# MBO.net
KiCad netlist of a schematic drawn in EAGLE
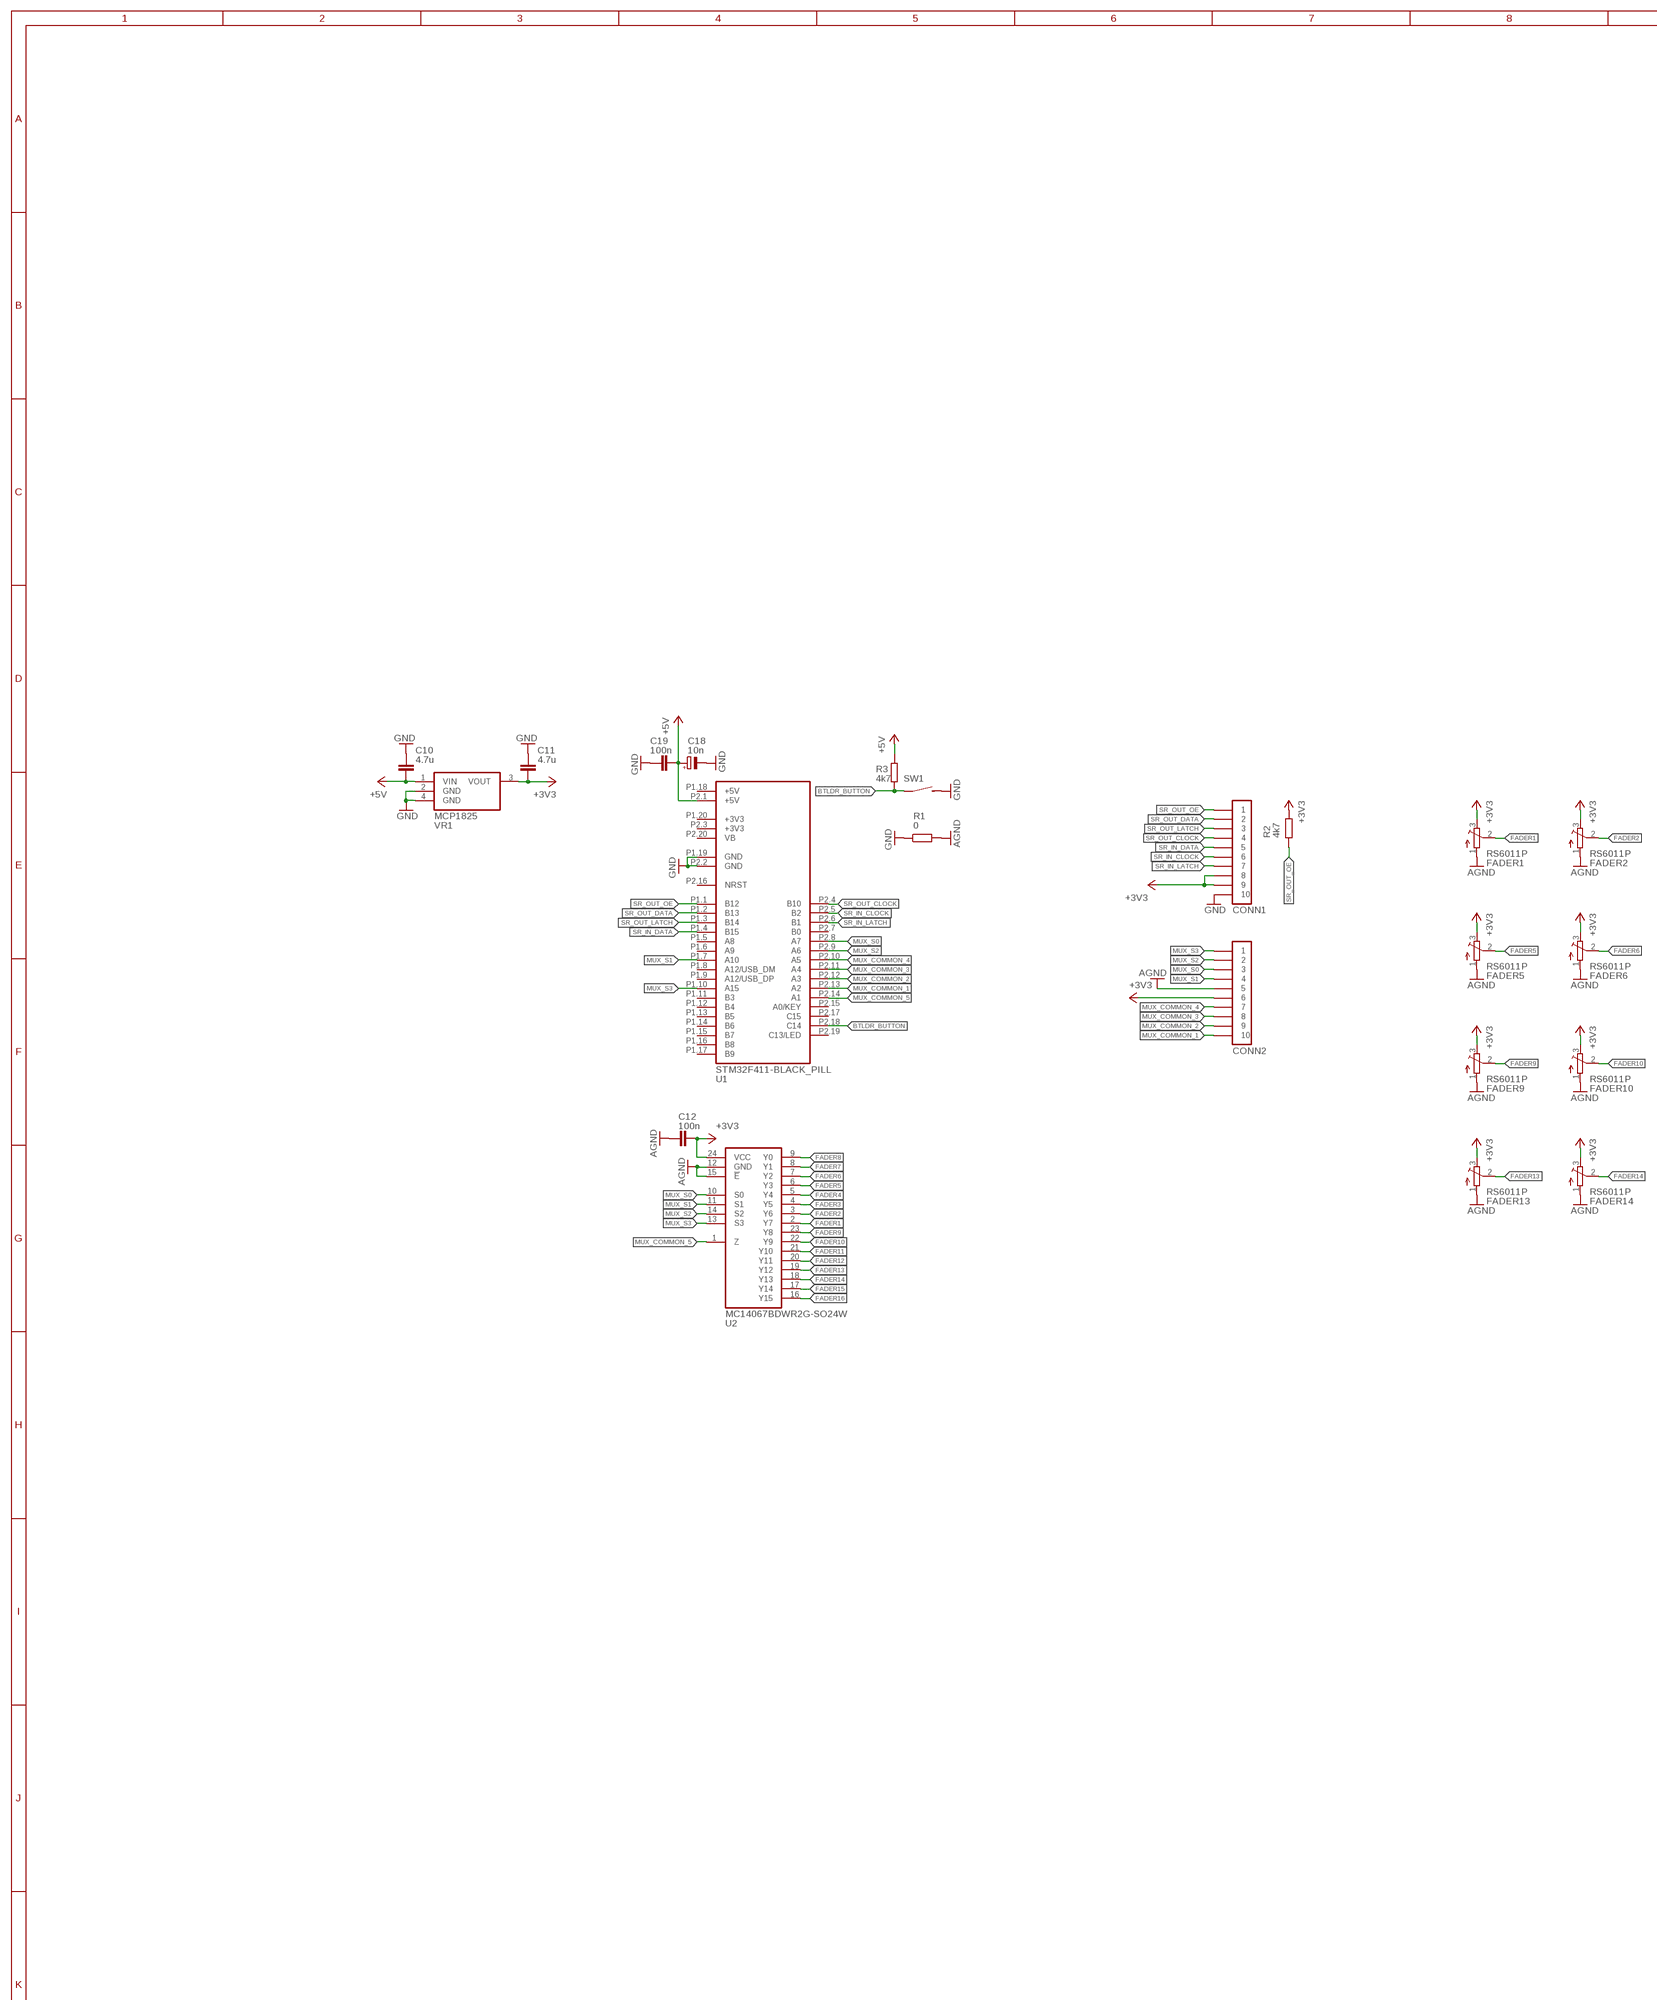
[diagram p0: schematic, sheet 1, part 1 of 3]
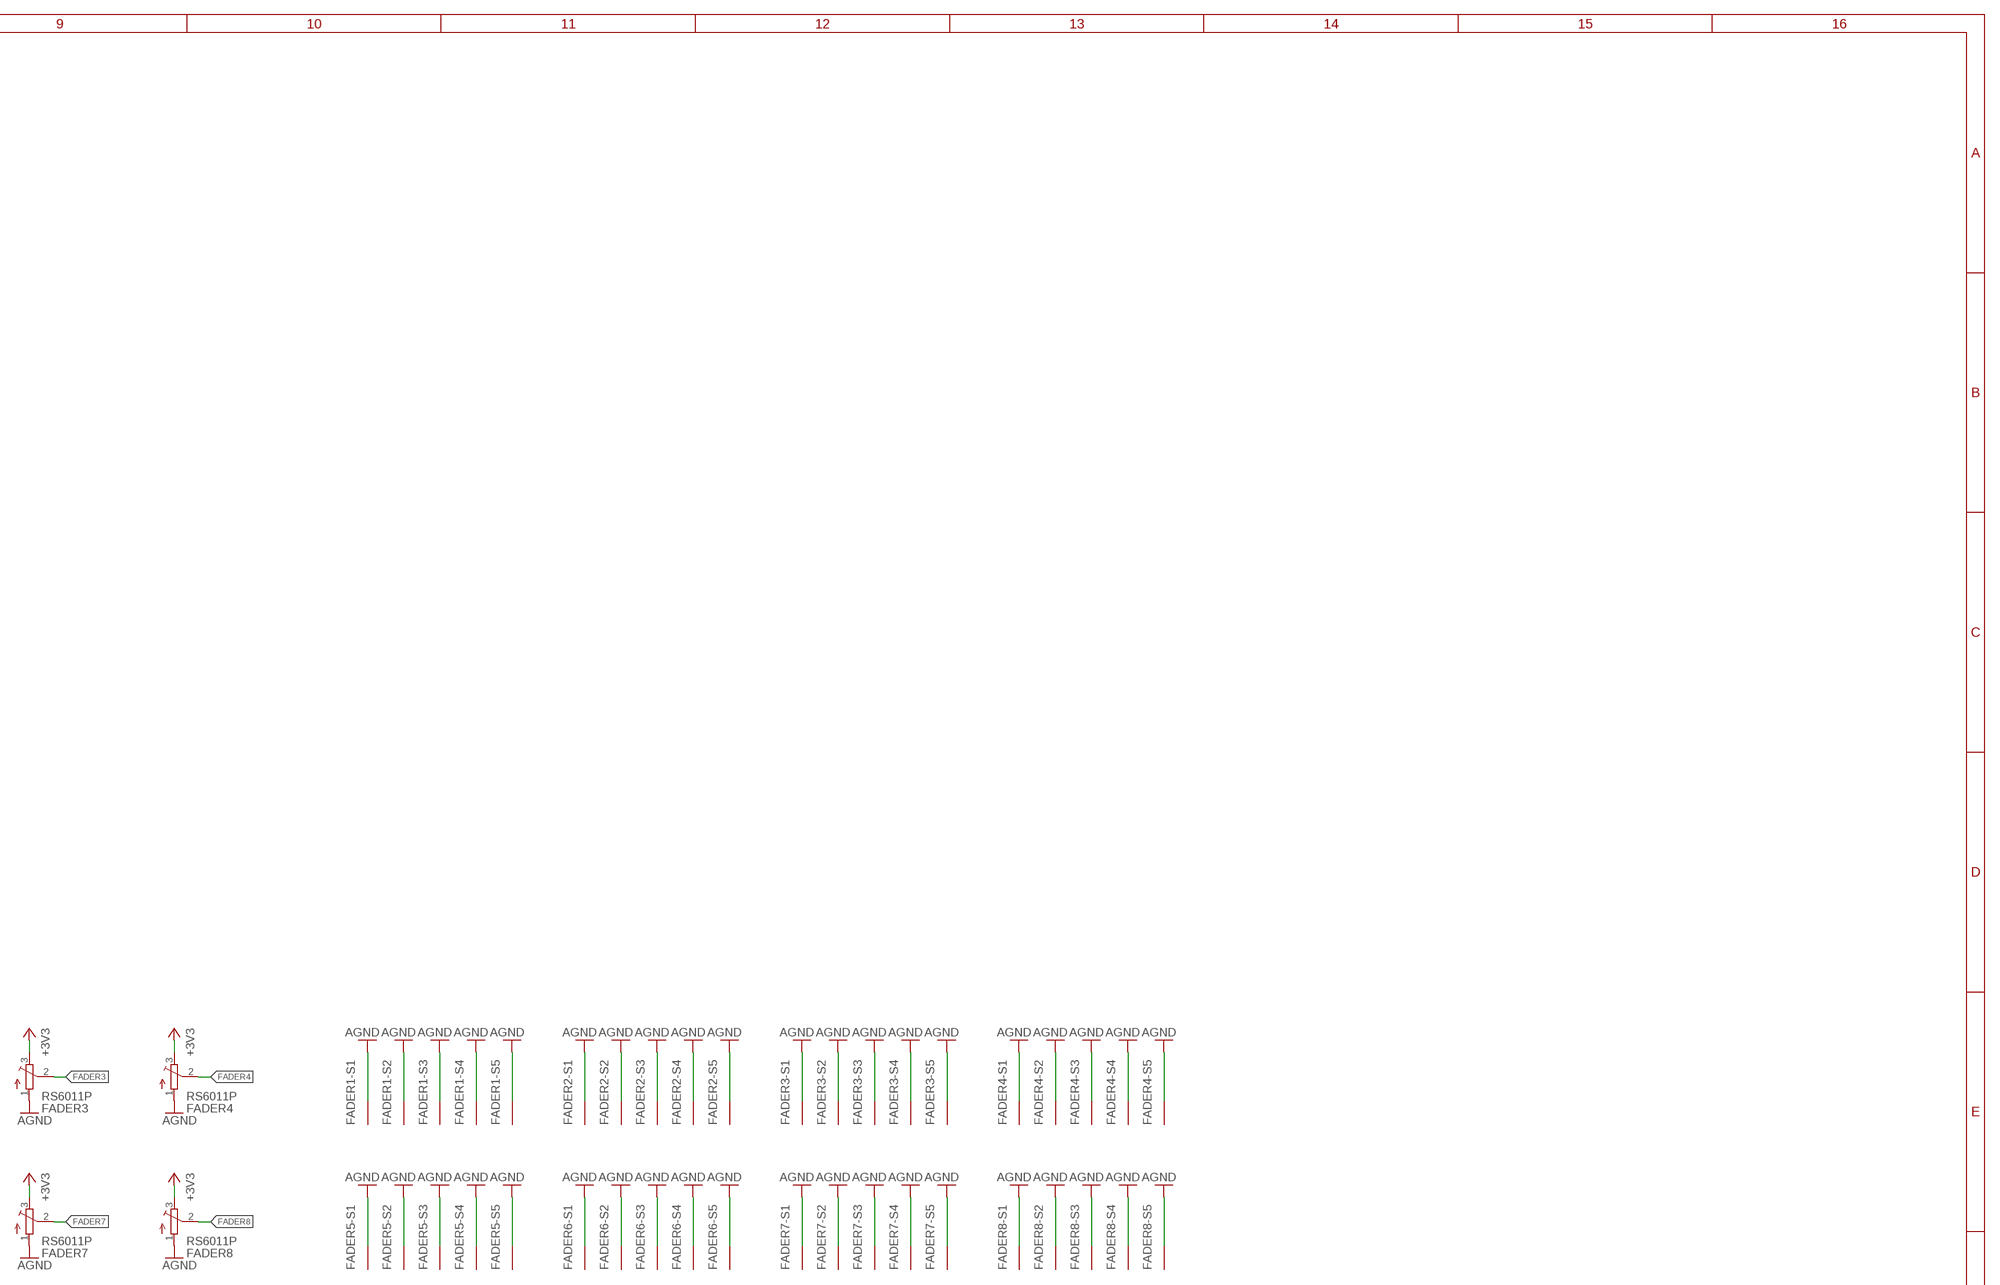
[diagram p1: schematic, sheet 1, part 2 of 3]
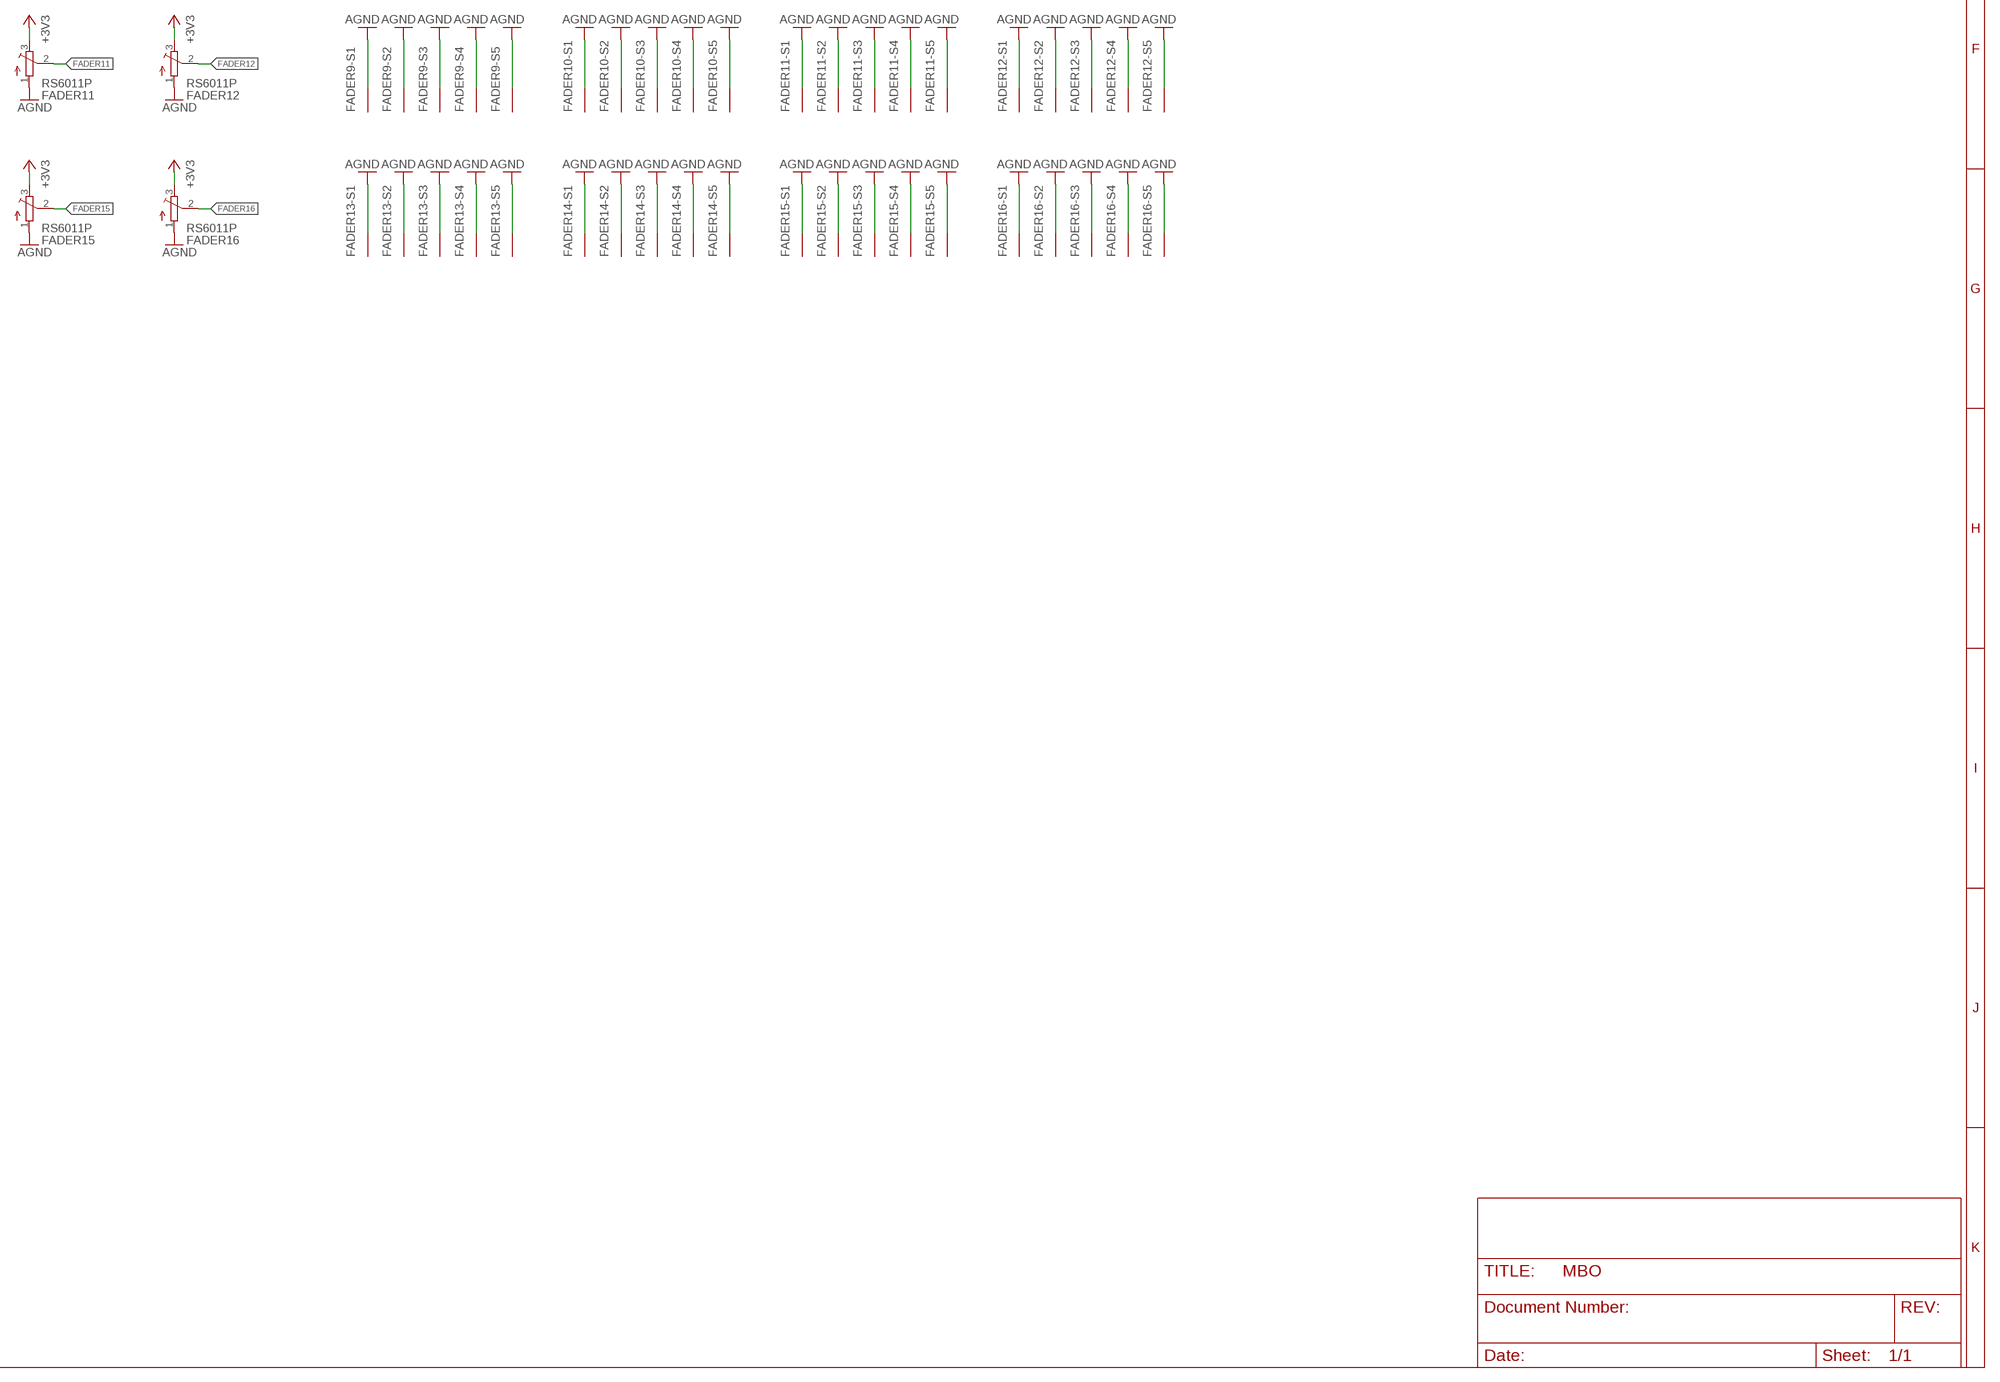
[diagram p2: schematic, sheet 1, part 3 of 3]

(export (version "E")
  (design (tool "Eeschema 10.0.6"))
  (components
    (comp (ref "C10")
      (value "4.7u")
      (footprint "eagle-import:C0805")
      (libsource (lib "eagle-import") (part "CAPACITOR-0805"))
    )
    (comp (ref "C11")
      (value "4.7u")
      (footprint "eagle-import:C0805")
      (libsource (lib "eagle-import") (part "CAPACITOR-0805"))
    )
    (comp (ref "C12")
      (value "100n")
      (footprint "eagle-import:C0805")
      (libsource (lib "eagle-import") (part "CAPACITOR-0805"))
    )
    (comp (ref "C18")
      (value "10n")
      (footprint "eagle-import:C-TH-E-0401")
      (libsource (lib "eagle-import") (part "ELECTROLYTIC_CAPACITOR-C-TH-E-0401"))
    )
    (comp (ref "C19")
      (value "100n")
      (footprint "eagle-import:C0805")
      (libsource (lib "eagle-import") (part "CAPACITOR-0805"))
    )
    (comp (ref "CONN1")
      (value "PINHD-1X10-FFC-1MM-Z")
      (footprint "eagle-import:MOLEX-52271-1079")
      (fields (field (name "MANUFACTURER") "Molex") (field (name "MPN") "52271-1079"))
      (libsource (lib "eagle-import") (part "PINHD-1X10-FFC-1MM-Z"))
    )
    (comp (ref "CONN2")
      (value "PINHD-1X10-FFC-1MM-Z")
      (footprint "eagle-import:MOLEX-52271-1079")
      (fields (field (name "MANUFACTURER") "Molex") (field (name "MPN") "52271-1079"))
      (libsource (lib "eagle-import") (part "PINHD-1X10-FFC-1MM-Z"))
    )
    (comp (ref "FADER1")
      (value "RS6011P")
      (footprint "eagle-import:RS6011_P")
      (libsource (lib "eagle-import") (part "RS6011P"))
    )
    (comp (ref "FADER2")
      (value "RS6011P")
      (footprint "eagle-import:RS6011_P")
      (libsource (lib "eagle-import") (part "RS6011P"))
    )
    (comp (ref "FADER3")
      (value "RS6011P")
      (footprint "eagle-import:RS6011_P")
      (libsource (lib "eagle-import") (part "RS6011P"))
    )
    (comp (ref "FADER4")
      (value "RS6011P")
      (footprint "eagle-import:RS6011_P")
      (libsource (lib "eagle-import") (part "RS6011P"))
    )
    (comp (ref "FADER5")
      (value "RS6011P")
      (footprint "eagle-import:RS6011_P")
      (libsource (lib "eagle-import") (part "RS6011P"))
    )
    (comp (ref "FADER6")
      (value "RS6011P")
      (footprint "eagle-import:RS6011_P")
      (libsource (lib "eagle-import") (part "RS6011P"))
    )
    (comp (ref "FADER7")
      (value "RS6011P")
      (footprint "eagle-import:RS6011_P")
      (libsource (lib "eagle-import") (part "RS6011P"))
    )
    (comp (ref "FADER8")
      (value "RS6011P")
      (footprint "eagle-import:RS6011_P")
      (libsource (lib "eagle-import") (part "RS6011P"))
    )
    (comp (ref "FADER9")
      (value "RS6011P")
      (footprint "eagle-import:RS6011_P")
      (libsource (lib "eagle-import") (part "RS6011P"))
    )
    (comp (ref "FADER10")
      (value "RS6011P")
      (footprint "eagle-import:RS6011_P")
      (libsource (lib "eagle-import") (part "RS6011P"))
    )
    (comp (ref "FADER11")
      (value "RS6011P")
      (footprint "eagle-import:RS6011_P")
      (libsource (lib "eagle-import") (part "RS6011P"))
    )
    (comp (ref "FADER12")
      (value "RS6011P")
      (footprint "eagle-import:RS6011_P")
      (libsource (lib "eagle-import") (part "RS6011P"))
    )
    (comp (ref "FADER13")
      (value "RS6011P")
      (footprint "eagle-import:RS6011_P")
      (libsource (lib "eagle-import") (part "RS6011P"))
    )
    (comp (ref "FADER14")
      (value "RS6011P")
      (footprint "eagle-import:RS6011_P")
      (libsource (lib "eagle-import") (part "RS6011P"))
    )
    (comp (ref "FADER15")
      (value "RS6011P")
      (footprint "eagle-import:RS6011_P")
      (libsource (lib "eagle-import") (part "RS6011P"))
    )
    (comp (ref "FADER16")
      (value "RS6011P")
      (footprint "eagle-import:RS6011_P")
      (libsource (lib "eagle-import") (part "RS6011P"))
    )
    (comp (ref "R1")
      (value "0")
      (footprint "eagle-import:R0805")
      (libsource (lib "eagle-import") (part "RESISTOR-0805"))
    )
    (comp (ref "R2")
      (value "4k7")
      (footprint "eagle-import:R0805")
      (libsource (lib "eagle-import") (part "RESISTOR-0805"))
    )
    (comp (ref "R3")
      (value "4k7")
      (footprint "eagle-import:R0805")
      (libsource (lib "eagle-import") (part "RESISTOR-0805"))
    )
    (comp (ref "SW1")
      (value "SWITCH-TACT-TH-6X6MM")
      (footprint "eagle-import:TACT_SW_6X6MM")
      (libsource (lib "eagle-import") (part "SWITCH-TACT-TH-6X6MM"))
    )
    (comp (ref "U1")
      (value "STM32F411-BLACK_PILL")
      (footprint "eagle-import:STM32F411-BLACK_PILL")
      (libsource (lib "eagle-import") (part "STM32F411-BLACK_PILL"))
    )
    (comp (ref "U2")
      (value "MC14067BDWR2G-SO24W")
      (footprint "eagle-import:SO24-W")
      (fields (field (name "MANUFACTURER") "ON Semiconductor") (field (name "MPN") "MC14067BDWR2G"))
      (libsource (lib "eagle-import") (part "MC14067BDWR2G-SO24W"))
    )
    (comp (ref "VR1")
      (value "MCP1825")
      (footprint "eagle-import:SOT223")
      (fields (field (name "MANUFACTURER") "Microchip") (field (name "MPN") "MCP1825S-3302E/DB"))
      (libsource (lib "eagle-import") (part "MCP1825"))
    )
  )
  (nets
    (net (code "1") (name "+3V3") (class "Default")
      (node (ref "C11") (pin "1") (pinfunction "1_1") (pintype "passive"))
      (node (ref "C12") (pin "1") (pinfunction "1_1") (pintype "passive"))
      (node (ref "CONN1") (pin "8") (pinfunction "8_8") (pintype "passive"))
      (node (ref "CONN1") (pin "9") (pinfunction "9_9") (pintype "passive"))
      (node (ref "CONN2") (pin "6") (pinfunction "6_6") (pintype "passive"))
      (node (ref "FADER1") (pin "3") (pinfunction "3_3") (pintype "passive"))
      (node (ref "FADER10") (pin "3") (pinfunction "3_3") (pintype "passive"))
      (node (ref "FADER11") (pin "3") (pinfunction "3_3") (pintype "passive"))
      (node (ref "FADER12") (pin "3") (pinfunction "3_3") (pintype "passive"))
      (node (ref "FADER13") (pin "3") (pinfunction "3_3") (pintype "passive"))
      (node (ref "FADER14") (pin "3") (pinfunction "3_3") (pintype "passive"))
      (node (ref "FADER15") (pin "3") (pinfunction "3_3") (pintype "passive"))
      (node (ref "FADER16") (pin "3") (pinfunction "3_3") (pintype "passive"))
      (node (ref "FADER2") (pin "3") (pinfunction "3_3") (pintype "passive"))
      (node (ref "FADER3") (pin "3") (pinfunction "3_3") (pintype "passive"))
      (node (ref "FADER4") (pin "3") (pinfunction "3_3") (pintype "passive"))
      (node (ref "FADER5") (pin "3") (pinfunction "3_3") (pintype "passive"))
      (node (ref "FADER6") (pin "3") (pinfunction "3_3") (pintype "passive"))
      (node (ref "FADER7") (pin "3") (pinfunction "3_3") (pintype "passive"))
      (node (ref "FADER8") (pin "3") (pinfunction "3_3") (pintype "passive"))
      (node (ref "FADER9") (pin "3") (pinfunction "3_3") (pintype "passive"))
      (node (ref "R2") (pin "2") (pinfunction "2_2") (pintype "passive"))
      (node (ref "U2") (pin "24") (pinfunction "VCC_24") (pintype "passive"))
      (node (ref "VR1") (pin "3") (pinfunction "VOUT_3") (pintype "passive"))
    )
    (net (code "2") (name "+5V") (class "Default")
      (node (ref "C10") (pin "1") (pinfunction "1_1") (pintype "passive"))
      (node (ref "C18") (pin "+") (pinfunction "+_+") (pintype "passive"))
      (node (ref "C19") (pin "1") (pinfunction "1_1") (pintype "passive"))
      (node (ref "R3") (pin "1") (pinfunction "1_1") (pintype "passive"))
      (node (ref "U1") (pin "P2.1") (pinfunction "+5V_P2.1") (pintype "bidirectional"))
      (node (ref "VR1") (pin "1") (pinfunction "VIN_1") (pintype "passive"))
    )
    (net (code "3") (name "AGND") (class "Default")
      (node (ref "C12") (pin "2") (pinfunction "2_2") (pintype "passive"))
      (node (ref "CONN2") (pin "5") (pinfunction "5_5") (pintype "passive"))
      (node (ref "FADER1") (pin "1") (pinfunction "1_1") (pintype "passive"))
      (node (ref "FADER1") (pin "S1") (pinfunction "S_S1") (pintype "passive"))
      (node (ref "FADER1") (pin "S2") (pinfunction "S_S2") (pintype "passive"))
      (node (ref "FADER1") (pin "S3") (pinfunction "S_S3") (pintype "passive"))
      (node (ref "FADER1") (pin "S4") (pinfunction "S_S4") (pintype "passive"))
      (node (ref "FADER1") (pin "S5") (pinfunction "S_S5") (pintype "passive"))
      (node (ref "FADER10") (pin "1") (pinfunction "1_1") (pintype "passive"))
      (node (ref "FADER10") (pin "S1") (pinfunction "S_S1") (pintype "passive"))
      (node (ref "FADER10") (pin "S2") (pinfunction "S_S2") (pintype "passive"))
      (node (ref "FADER10") (pin "S3") (pinfunction "S_S3") (pintype "passive"))
      (node (ref "FADER10") (pin "S4") (pinfunction "S_S4") (pintype "passive"))
      (node (ref "FADER10") (pin "S5") (pinfunction "S_S5") (pintype "passive"))
      (node (ref "FADER11") (pin "1") (pinfunction "1_1") (pintype "passive"))
      (node (ref "FADER11") (pin "S1") (pinfunction "S_S1") (pintype "passive"))
      (node (ref "FADER11") (pin "S2") (pinfunction "S_S2") (pintype "passive"))
      (node (ref "FADER11") (pin "S3") (pinfunction "S_S3") (pintype "passive"))
      (node (ref "FADER11") (pin "S4") (pinfunction "S_S4") (pintype "passive"))
      (node (ref "FADER11") (pin "S5") (pinfunction "S_S5") (pintype "passive"))
      (node (ref "FADER12") (pin "1") (pinfunction "1_1") (pintype "passive"))
      (node (ref "FADER12") (pin "S1") (pinfunction "S_S1") (pintype "passive"))
      (node (ref "FADER12") (pin "S2") (pinfunction "S_S2") (pintype "passive"))
      (node (ref "FADER12") (pin "S3") (pinfunction "S_S3") (pintype "passive"))
      (node (ref "FADER12") (pin "S4") (pinfunction "S_S4") (pintype "passive"))
      (node (ref "FADER12") (pin "S5") (pinfunction "S_S5") (pintype "passive"))
      (node (ref "FADER13") (pin "1") (pinfunction "1_1") (pintype "passive"))
      (node (ref "FADER13") (pin "S1") (pinfunction "S_S1") (pintype "passive"))
      (node (ref "FADER13") (pin "S2") (pinfunction "S_S2") (pintype "passive"))
      (node (ref "FADER13") (pin "S3") (pinfunction "S_S3") (pintype "passive"))
      (node (ref "FADER13") (pin "S4") (pinfunction "S_S4") (pintype "passive"))
      (node (ref "FADER13") (pin "S5") (pinfunction "S_S5") (pintype "passive"))
      (node (ref "FADER14") (pin "1") (pinfunction "1_1") (pintype "passive"))
      (node (ref "FADER14") (pin "S1") (pinfunction "S_S1") (pintype "passive"))
      (node (ref "FADER14") (pin "S2") (pinfunction "S_S2") (pintype "passive"))
      (node (ref "FADER14") (pin "S3") (pinfunction "S_S3") (pintype "passive"))
      (node (ref "FADER14") (pin "S4") (pinfunction "S_S4") (pintype "passive"))
      (node (ref "FADER14") (pin "S5") (pinfunction "S_S5") (pintype "passive"))
      (node (ref "FADER15") (pin "1") (pinfunction "1_1") (pintype "passive"))
      (node (ref "FADER15") (pin "S1") (pinfunction "S_S1") (pintype "passive"))
      (node (ref "FADER15") (pin "S2") (pinfunction "S_S2") (pintype "passive"))
      (node (ref "FADER15") (pin "S3") (pinfunction "S_S3") (pintype "passive"))
      (node (ref "FADER15") (pin "S4") (pinfunction "S_S4") (pintype "passive"))
      (node (ref "FADER15") (pin "S5") (pinfunction "S_S5") (pintype "passive"))
      (node (ref "FADER16") (pin "1") (pinfunction "1_1") (pintype "passive"))
      (node (ref "FADER16") (pin "S1") (pinfunction "S_S1") (pintype "passive"))
      (node (ref "FADER16") (pin "S2") (pinfunction "S_S2") (pintype "passive"))
      (node (ref "FADER16") (pin "S3") (pinfunction "S_S3") (pintype "passive"))
      (node (ref "FADER16") (pin "S4") (pinfunction "S_S4") (pintype "passive"))
      (node (ref "FADER16") (pin "S5") (pinfunction "S_S5") (pintype "passive"))
      (node (ref "FADER2") (pin "1") (pinfunction "1_1") (pintype "passive"))
      (node (ref "FADER2") (pin "S1") (pinfunction "S_S1") (pintype "passive"))
      (node (ref "FADER2") (pin "S2") (pinfunction "S_S2") (pintype "passive"))
      (node (ref "FADER2") (pin "S3") (pinfunction "S_S3") (pintype "passive"))
      (node (ref "FADER2") (pin "S4") (pinfunction "S_S4") (pintype "passive"))
      (node (ref "FADER2") (pin "S5") (pinfunction "S_S5") (pintype "passive"))
      (node (ref "FADER3") (pin "1") (pinfunction "1_1") (pintype "passive"))
      (node (ref "FADER3") (pin "S1") (pinfunction "S_S1") (pintype "passive"))
      (node (ref "FADER3") (pin "S2") (pinfunction "S_S2") (pintype "passive"))
      (node (ref "FADER3") (pin "S3") (pinfunction "S_S3") (pintype "passive"))
      (node (ref "FADER3") (pin "S4") (pinfunction "S_S4") (pintype "passive"))
      (node (ref "FADER3") (pin "S5") (pinfunction "S_S5") (pintype "passive"))
      (node (ref "FADER4") (pin "1") (pinfunction "1_1") (pintype "passive"))
      (node (ref "FADER4") (pin "S1") (pinfunction "S_S1") (pintype "passive"))
      (node (ref "FADER4") (pin "S2") (pinfunction "S_S2") (pintype "passive"))
      (node (ref "FADER4") (pin "S3") (pinfunction "S_S3") (pintype "passive"))
      (node (ref "FADER4") (pin "S4") (pinfunction "S_S4") (pintype "passive"))
      (node (ref "FADER4") (pin "S5") (pinfunction "S_S5") (pintype "passive"))
      (node (ref "FADER5") (pin "1") (pinfunction "1_1") (pintype "passive"))
      (node (ref "FADER5") (pin "S1") (pinfunction "S_S1") (pintype "passive"))
      (node (ref "FADER5") (pin "S2") (pinfunction "S_S2") (pintype "passive"))
      (node (ref "FADER5") (pin "S3") (pinfunction "S_S3") (pintype "passive"))
      (node (ref "FADER5") (pin "S4") (pinfunction "S_S4") (pintype "passive"))
      (node (ref "FADER5") (pin "S5") (pinfunction "S_S5") (pintype "passive"))
      (node (ref "FADER6") (pin "1") (pinfunction "1_1") (pintype "passive"))
      (node (ref "FADER6") (pin "S1") (pinfunction "S_S1") (pintype "passive"))
      (node (ref "FADER6") (pin "S2") (pinfunction "S_S2") (pintype "passive"))
      (node (ref "FADER6") (pin "S3") (pinfunction "S_S3") (pintype "passive"))
      (node (ref "FADER6") (pin "S4") (pinfunction "S_S4") (pintype "passive"))
      (node (ref "FADER6") (pin "S5") (pinfunction "S_S5") (pintype "passive"))
      (node (ref "FADER7") (pin "1") (pinfunction "1_1") (pintype "passive"))
      (node (ref "FADER7") (pin "S1") (pinfunction "S_S1") (pintype "passive"))
      (node (ref "FADER7") (pin "S2") (pinfunction "S_S2") (pintype "passive"))
      (node (ref "FADER7") (pin "S3") (pinfunction "S_S3") (pintype "passive"))
      (node (ref "FADER7") (pin "S4") (pinfunction "S_S4") (pintype "passive"))
      (node (ref "FADER7") (pin "S5") (pinfunction "S_S5") (pintype "passive"))
      (node (ref "FADER8") (pin "1") (pinfunction "1_1") (pintype "passive"))
      (node (ref "FADER8") (pin "S1") (pinfunction "S_S1") (pintype "passive"))
      (node (ref "FADER8") (pin "S2") (pinfunction "S_S2") (pintype "passive"))
      (node (ref "FADER8") (pin "S3") (pinfunction "S_S3") (pintype "passive"))
      (node (ref "FADER8") (pin "S4") (pinfunction "S_S4") (pintype "passive"))
      (node (ref "FADER8") (pin "S5") (pinfunction "S_S5") (pintype "passive"))
      (node (ref "FADER9") (pin "1") (pinfunction "1_1") (pintype "passive"))
      (node (ref "FADER9") (pin "S1") (pinfunction "S_S1") (pintype "passive"))
      (node (ref "FADER9") (pin "S2") (pinfunction "S_S2") (pintype "passive"))
      (node (ref "FADER9") (pin "S3") (pinfunction "S_S3") (pintype "passive"))
      (node (ref "FADER9") (pin "S4") (pinfunction "S_S4") (pintype "passive"))
      (node (ref "FADER9") (pin "S5") (pinfunction "S_S5") (pintype "passive"))
      (node (ref "R1") (pin "2") (pinfunction "2_2") (pintype "passive"))
      (node (ref "U2") (pin "12") (pinfunction "GND_12") (pintype "passive"))
      (node (ref "U2") (pin "15") (pinfunction "~{E}_15") (pintype "input"))
    )
    (net (code "4") (name "BTLDR_BUTTON") (class "Default")
      (node (ref "R3") (pin "2") (pinfunction "2_2") (pintype "passive"))
      (node (ref "SW1") (pin "A1") (pinfunction "1_A1") (pintype "passive"))
      (node (ref "U1") (pin "P2.18") (pinfunction "C14_P2.18") (pintype "bidirectional"))
    )
    (net (code "5") (name "FADER1") (class "Default")
      (node (ref "FADER1") (pin "2") (pinfunction "2_2") (pintype "passive"))
      (node (ref "U2") (pin "2") (pinfunction "Y7_2") (pintype "bidirectional"))
    )
    (net (code "6") (name "FADER2") (class "Default")
      (node (ref "FADER2") (pin "2") (pinfunction "2_2") (pintype "passive"))
      (node (ref "U2") (pin "3") (pinfunction "Y6_3") (pintype "bidirectional"))
    )
    (net (code "7") (name "FADER3") (class "Default")
      (node (ref "FADER3") (pin "2") (pinfunction "2_2") (pintype "passive"))
      (node (ref "U2") (pin "4") (pinfunction "Y5_4") (pintype "bidirectional"))
    )
    (net (code "8") (name "FADER4") (class "Default")
      (node (ref "FADER4") (pin "2") (pinfunction "2_2") (pintype "passive"))
      (node (ref "U2") (pin "5") (pinfunction "Y4_5") (pintype "bidirectional"))
    )
    (net (code "9") (name "FADER5") (class "Default")
      (node (ref "FADER5") (pin "2") (pinfunction "2_2") (pintype "passive"))
      (node (ref "U2") (pin "6") (pinfunction "Y3_6") (pintype "bidirectional"))
    )
    (net (code "10") (name "FADER6") (class "Default")
      (node (ref "FADER6") (pin "2") (pinfunction "2_2") (pintype "passive"))
      (node (ref "U2") (pin "7") (pinfunction "Y2_7") (pintype "bidirectional"))
    )
    (net (code "11") (name "FADER7") (class "Default")
      (node (ref "FADER7") (pin "2") (pinfunction "2_2") (pintype "passive"))
      (node (ref "U2") (pin "8") (pinfunction "Y1_8") (pintype "bidirectional"))
    )
    (net (code "12") (name "FADER8") (class "Default")
      (node (ref "FADER8") (pin "2") (pinfunction "2_2") (pintype "passive"))
      (node (ref "U2") (pin "9") (pinfunction "Y0_9") (pintype "bidirectional"))
    )
    (net (code "13") (name "FADER9") (class "Default")
      (node (ref "FADER9") (pin "2") (pinfunction "2_2") (pintype "passive"))
      (node (ref "U2") (pin "23") (pinfunction "Y8_23") (pintype "bidirectional"))
    )
    (net (code "14") (name "FADER10") (class "Default")
      (node (ref "FADER10") (pin "2") (pinfunction "2_2") (pintype "passive"))
      (node (ref "U2") (pin "22") (pinfunction "Y9_22") (pintype "bidirectional"))
    )
    (net (code "15") (name "FADER11") (class "Default")
      (node (ref "FADER11") (pin "2") (pinfunction "2_2") (pintype "passive"))
      (node (ref "U2") (pin "21") (pinfunction "Y10_21") (pintype "bidirectional"))
    )
    (net (code "16") (name "FADER12") (class "Default")
      (node (ref "FADER12") (pin "2") (pinfunction "2_2") (pintype "passive"))
      (node (ref "U2") (pin "20") (pinfunction "Y11_20") (pintype "bidirectional"))
    )
    (net (code "17") (name "FADER13") (class "Default")
      (node (ref "FADER13") (pin "2") (pinfunction "2_2") (pintype "passive"))
      (node (ref "U2") (pin "19") (pinfunction "Y12_19") (pintype "bidirectional"))
    )
    (net (code "18") (name "FADER14") (class "Default")
      (node (ref "FADER14") (pin "2") (pinfunction "2_2") (pintype "passive"))
      (node (ref "U2") (pin "18") (pinfunction "Y13_18") (pintype "bidirectional"))
    )
    (net (code "19") (name "FADER15") (class "Default")
      (node (ref "FADER15") (pin "2") (pinfunction "2_2") (pintype "passive"))
      (node (ref "U2") (pin "17") (pinfunction "Y14_17") (pintype "bidirectional"))
    )
    (net (code "20") (name "FADER16") (class "Default")
      (node (ref "FADER16") (pin "2") (pinfunction "2_2") (pintype "passive"))
      (node (ref "U2") (pin "16") (pinfunction "Y15_16") (pintype "bidirectional"))
    )
    (net (code "21") (name "GND") (class "Default")
      (node (ref "C10") (pin "2") (pinfunction "2_2") (pintype "passive"))
      (node (ref "C11") (pin "2") (pinfunction "2_2") (pintype "passive"))
      (node (ref "C18") (pin "-") (pinfunction "-_-") (pintype "passive"))
      (node (ref "C19") (pin "2") (pinfunction "2_2") (pintype "passive"))
      (node (ref "CONN1") (pin "10") (pinfunction "10_10") (pintype "passive"))
      (node (ref "R1") (pin "1") (pinfunction "1_1") (pintype "passive"))
      (node (ref "SW1") (pin "B1") (pinfunction "2_B1") (pintype "passive"))
      (node (ref "U1") (pin "P1.19") (pinfunction "GND_P1.19") (pintype "bidirectional"))
      (node (ref "U1") (pin "P2.2") (pinfunction "GND_P2.2") (pintype "bidirectional"))
      (node (ref "VR1") (pin "2") (pinfunction "GND_2") (pintype "passive"))
      (node (ref "VR1") (pin "4") (pinfunction "GND_4") (pintype "passive"))
    )
    (net (code "22") (name "MUX_COMMON_1") (class "Default")
      (node (ref "CONN2") (pin "10") (pinfunction "10_10") (pintype "passive"))
      (node (ref "U1") (pin "P2.13") (pinfunction "A2_P2.13") (pintype "bidirectional"))
    )
    (net (code "23") (name "MUX_COMMON_2") (class "Default")
      (node (ref "CONN2") (pin "9") (pinfunction "9_9") (pintype "passive"))
      (node (ref "U1") (pin "P2.12") (pinfunction "A3_P2.12") (pintype "bidirectional"))
    )
    (net (code "24") (name "MUX_COMMON_3") (class "Default")
      (node (ref "CONN2") (pin "8") (pinfunction "8_8") (pintype "passive"))
      (node (ref "U1") (pin "P2.11") (pinfunction "A4_P2.11") (pintype "bidirectional"))
    )
    (net (code "25") (name "MUX_COMMON_4") (class "Default")
      (node (ref "CONN2") (pin "7") (pinfunction "7_7") (pintype "passive"))
      (node (ref "U1") (pin "P2.10") (pinfunction "A5_P2.10") (pintype "bidirectional"))
    )
    (net (code "26") (name "MUX_COMMON_5") (class "Default")
      (node (ref "U1") (pin "P2.14") (pinfunction "A1_P2.14") (pintype "bidirectional"))
      (node (ref "U2") (pin "1") (pinfunction "Z_1") (pintype "bidirectional"))
    )
    (net (code "27") (name "MUX_S0") (class "Default")
      (node (ref "CONN2") (pin "3") (pinfunction "3_3") (pintype "passive"))
      (node (ref "U1") (pin "P2.8") (pinfunction "A7_P2.8") (pintype "bidirectional"))
      (node (ref "U2") (pin "10") (pinfunction "S0_10") (pintype "input"))
    )
    (net (code "28") (name "MUX_S1") (class "Default")
      (node (ref "CONN2") (pin "4") (pinfunction "4_4") (pintype "passive"))
      (node (ref "U1") (pin "P1.7") (pinfunction "A10_P1.7") (pintype "bidirectional"))
      (node (ref "U2") (pin "11") (pinfunction "S1_11") (pintype "input"))
    )
    (net (code "29") (name "MUX_S2") (class "Default")
      (node (ref "CONN2") (pin "2") (pinfunction "2_2") (pintype "passive"))
      (node (ref "U1") (pin "P2.9") (pinfunction "A6_P2.9") (pintype "bidirectional"))
      (node (ref "U2") (pin "14") (pinfunction "S2_14") (pintype "input"))
    )
    (net (code "30") (name "MUX_S3") (class "Default")
      (node (ref "CONN2") (pin "1") (pinfunction "1_1") (pintype "passive"))
      (node (ref "U1") (pin "P1.10") (pinfunction "A15_P1.10") (pintype "bidirectional"))
      (node (ref "U2") (pin "13") (pinfunction "S3_13") (pintype "input"))
    )
    (net (code "31") (name "SR_IN_CLOCK") (class "Default")
      (node (ref "CONN1") (pin "6") (pinfunction "6_6") (pintype "passive"))
      (node (ref "U1") (pin "P2.5") (pinfunction "B2_P2.5") (pintype "bidirectional"))
    )
    (net (code "32") (name "SR_IN_DATA") (class "Default")
      (node (ref "CONN1") (pin "5") (pinfunction "5_5") (pintype "passive"))
      (node (ref "U1") (pin "P1.4") (pinfunction "B15_P1.4") (pintype "bidirectional"))
    )
    (net (code "33") (name "SR_IN_LATCH") (class "Default")
      (node (ref "CONN1") (pin "7") (pinfunction "7_7") (pintype "passive"))
      (node (ref "U1") (pin "P2.6") (pinfunction "B1_P2.6") (pintype "bidirectional"))
    )
    (net (code "34") (name "SR_OUT_CLOCK") (class "Default")
      (node (ref "CONN1") (pin "4") (pinfunction "4_4") (pintype "passive"))
      (node (ref "U1") (pin "P2.4") (pinfunction "B10_P2.4") (pintype "bidirectional"))
    )
    (net (code "35") (name "SR_OUT_DATA") (class "Default")
      (node (ref "CONN1") (pin "2") (pinfunction "2_2") (pintype "passive"))
      (node (ref "U1") (pin "P1.2") (pinfunction "B13_P1.2") (pintype "bidirectional"))
    )
    (net (code "36") (name "SR_OUT_LATCH") (class "Default")
      (node (ref "CONN1") (pin "3") (pinfunction "3_3") (pintype "passive"))
      (node (ref "U1") (pin "P1.3") (pinfunction "B14_P1.3") (pintype "bidirectional"))
    )
    (net (code "37") (name "SR_OUT_OE") (class "Default")
      (node (ref "CONN1") (pin "1") (pinfunction "1_1") (pintype "passive"))
      (node (ref "R2") (pin "1") (pinfunction "1_1") (pintype "passive"))
      (node (ref "U1") (pin "P1.1") (pinfunction "B12_P1.1") (pintype "bidirectional"))
    )
    (net (code "38") (name "unconnected-(U1-+3V3-PadP1.20)") (class "Default")
      (node (ref "U1") (pin "P1.20") (pinfunction "+3V3_P1.20") (pintype "bidirectional"))
    )
    (net (code "39") (name "unconnected-(U1-+3V3-PadP2.3)") (class "Default")
      (node (ref "U1") (pin "P2.3") (pinfunction "+3V3_P2.3") (pintype "bidirectional"))
    )
    (net (code "40") (name "unconnected-(U1-+5V-PadP1.18)") (class "Default")
      (node (ref "U1") (pin "P1.18") (pinfunction "+5V_P1.18") (pintype "bidirectional"))
    )
    (net (code "41") (name "unconnected-(U1-A0{slash}KEY-PadP2.15)") (class "Default")
      (node (ref "U1") (pin "P2.15") (pinfunction "A0/KEY_P2.15") (pintype "bidirectional"))
    )
    (net (code "42") (name "unconnected-(U1-A8-PadP1.5)") (class "Default")
      (node (ref "U1") (pin "P1.5") (pinfunction "A8_P1.5") (pintype "bidirectional"))
    )
    (net (code "43") (name "unconnected-(U1-A9-PadP1.6)") (class "Default")
      (node (ref "U1") (pin "P1.6") (pinfunction "A9_P1.6") (pintype "bidirectional"))
    )
    (net (code "44") (name "unconnected-(U1-A12{slash}USB_DM-PadP1.8)") (class "Default")
      (node (ref "U1") (pin "P1.8") (pinfunction "A12/USB_DM_P1.8") (pintype "bidirectional"))
    )
    (net (code "45") (name "unconnected-(U1-A12{slash}USB_DP-PadP1.9)") (class "Default")
      (node (ref "U1") (pin "P1.9") (pinfunction "A12/USB_DP_P1.9") (pintype "bidirectional"))
    )
    (net (code "46") (name "unconnected-(U1-B0-PadP2.7)") (class "Default")
      (node (ref "U1") (pin "P2.7") (pinfunction "B0_P2.7") (pintype "bidirectional"))
    )
    (net (code "47") (name "unconnected-(U1-B3-PadP1.11)") (class "Default")
      (node (ref "U1") (pin "P1.11") (pinfunction "B3_P1.11") (pintype "bidirectional"))
    )
    (net (code "48") (name "unconnected-(U1-B4-PadP1.12)") (class "Default")
      (node (ref "U1") (pin "P1.12") (pinfunction "B4_P1.12") (pintype "bidirectional"))
    )
    (net (code "49") (name "unconnected-(U1-B5-PadP1.13)") (class "Default")
      (node (ref "U1") (pin "P1.13") (pinfunction "B5_P1.13") (pintype "bidirectional"))
    )
    (net (code "50") (name "unconnected-(U1-B6-PadP1.14)") (class "Default")
      (node (ref "U1") (pin "P1.14") (pinfunction "B6_P1.14") (pintype "bidirectional"))
    )
    (net (code "51") (name "unconnected-(U1-B7-PadP1.15)") (class "Default")
      (node (ref "U1") (pin "P1.15") (pinfunction "B7_P1.15") (pintype "bidirectional"))
    )
    (net (code "52") (name "unconnected-(U1-B8-PadP1.16)") (class "Default")
      (node (ref "U1") (pin "P1.16") (pinfunction "B8_P1.16") (pintype "bidirectional"))
    )
    (net (code "53") (name "unconnected-(U1-B9-PadP1.17)") (class "Default")
      (node (ref "U1") (pin "P1.17") (pinfunction "B9_P1.17") (pintype "bidirectional"))
    )
    (net (code "54") (name "unconnected-(U1-C13{slash}LED-PadP2.19)") (class "Default")
      (node (ref "U1") (pin "P2.19") (pinfunction "C13/LED_P2.19") (pintype "bidirectional"))
    )
    (net (code "55") (name "unconnected-(U1-C15-PadP2.17)") (class "Default")
      (node (ref "U1") (pin "P2.17") (pinfunction "C15_P2.17") (pintype "bidirectional"))
    )
    (net (code "56") (name "unconnected-(U1-NRST-PadP2.16)") (class "Default")
      (node (ref "U1") (pin "P2.16") (pinfunction "NRST_P2.16") (pintype "bidirectional"))
    )
    (net (code "57") (name "unconnected-(U1-VB-PadP2.20)") (class "Default")
      (node (ref "U1") (pin "P2.20") (pinfunction "VB_P2.20") (pintype "bidirectional"))
    )
  )
)
